# AudioOutput.net
KiCad netlist of a schematic drawn in EAGLE
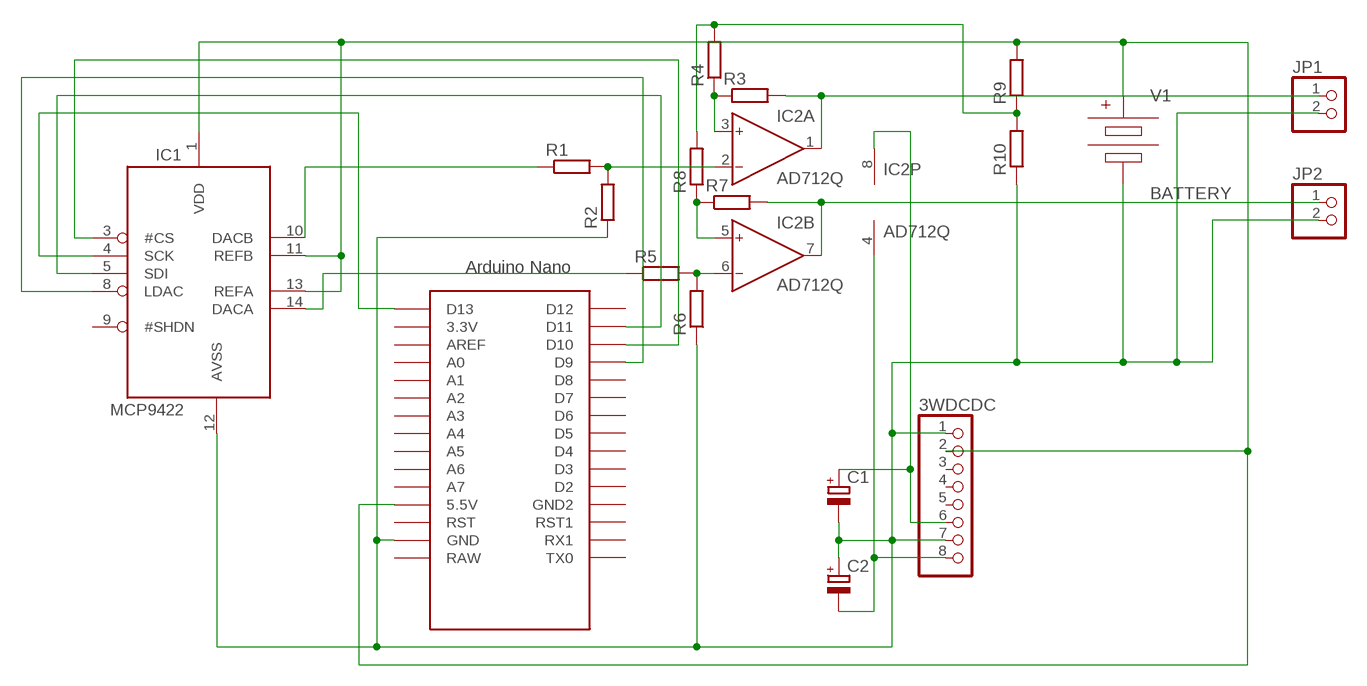
[diagram p0: schematic, sheet 1]

(export (version "E")
  (design (tool "Eeschema 10.0.6"))
  (components
    (comp (ref "3WDCDC")
      (value "PINHD-1X8")
      (footprint "eagle-import:1X08")
      (libsource (lib "eagle-import") (part "PINHD-1X8"))
    )
    (comp (ref "C1")
      (value "CPOL-EUE2.5-7")
      (footprint "eagle-import:E2,5-7")
      (libsource (lib "eagle-import") (part "CPOL-EUE2.5-7"))
    )
    (comp (ref "C2")
      (value "CPOL-EUE2.5-7")
      (footprint "eagle-import:E2,5-7")
      (libsource (lib "eagle-import") (part "CPOL-EUE2.5-7"))
    )
    (comp (ref "IC1")
      (value "MCP9422")
      (footprint "eagle-import:DIL14")
      (libsource (lib "eagle-import") (part "MCP9422"))
    )
    (comp (ref "IC2")
      (value "AD712Q")
      (footprint "eagle-import:DIL08")
      (fields (field (name "MF") "ALTERA CORPORATION") (field (name "MPN") "AD712AQ"))
      (libsource (lib "eagle-import") (part "AD712Q"))
    )
    (comp (ref "JP1")
      (value "PINHD-1X2")
      (footprint "eagle-import:1X02")
      (libsource (lib "eagle-import") (part "PINHD-1X2"))
    )
    (comp (ref "JP2")
      (value "PINHD-1X2")
      (footprint "eagle-import:1X02")
      (libsource (lib "eagle-import") (part "PINHD-1X2"))
    )
    (comp (ref "R1")
      (value "R-EU_0207/10")
      (footprint "eagle-import:0207_10")
      (libsource (lib "eagle-import") (part "R-EU_0207/10"))
    )
    (comp (ref "R2")
      (value "R-EU_0207/10")
      (footprint "eagle-import:0207_10")
      (libsource (lib "eagle-import") (part "R-EU_0207/10"))
    )
    (comp (ref "R3")
      (value "R-EU_0207/10")
      (footprint "eagle-import:0207_10")
      (libsource (lib "eagle-import") (part "R-EU_0207/10"))
    )
    (comp (ref "R4")
      (value "R-EU_0207/10")
      (footprint "eagle-import:0207_10")
      (libsource (lib "eagle-import") (part "R-EU_0207/10"))
    )
    (comp (ref "R5")
      (value "R-EU_0207/10")
      (footprint "eagle-import:0207_10")
      (libsource (lib "eagle-import") (part "R-EU_0207/10"))
    )
    (comp (ref "R6")
      (value "R-EU_0207/10")
      (footprint "eagle-import:0207_10")
      (libsource (lib "eagle-import") (part "R-EU_0207/10"))
    )
    (comp (ref "R7")
      (value "R-EU_0207/10")
      (footprint "eagle-import:0207_10")
      (libsource (lib "eagle-import") (part "R-EU_0207/10"))
    )
    (comp (ref "R8")
      (value "R-EU_0207/10")
      (footprint "eagle-import:0207_10")
      (libsource (lib "eagle-import") (part "R-EU_0207/10"))
    )
    (comp (ref "R9")
      (value "R-EU_0207/10")
      (footprint "eagle-import:0207_10")
      (libsource (lib "eagle-import") (part "R-EU_0207/10"))
    )
    (comp (ref "R10")
      (value "R-EU_0207/10")
      (footprint "eagle-import:0207_10")
      (libsource (lib "eagle-import") (part "R-EU_0207/10"))
    )
    (comp (ref "U$1")
      (value "NANO")
      (footprint "eagle-import:NANO")
      (libsource (lib "eagle-import") (part "NANO"))
    )
    (comp (ref "V1")
      (value "BATTERY")
      (footprint "eagle-import:3V60R")
      (libsource (lib "eagle-import") (part "BATTERY"))
    )
  )
  (nets
    (net (code "1") (name "Net-(IC1-#CS)") (class "Default")
      (node (ref "IC1") (pin "3") (pinfunction "#CS_3") (pintype "input"))
      (node (ref "U$1") (pin "D10") (pinfunction "D10_D10") (pintype "bidirectional"))
    )
    (net (code "2") (name "Net-(IC1-AVSS)") (class "Default")
      (node (ref "3WDCDC") (pin "1") (pinfunction "1_1") (pintype "passive"))
      (node (ref "3WDCDC") (pin "7") (pinfunction "7_7") (pintype "passive"))
      (node (ref "C1") (pin "-") (pinfunction "-_-") (pintype "passive"))
      (node (ref "C2") (pin "+") (pinfunction "+_+") (pintype "passive"))
      (node (ref "IC1") (pin "12") (pinfunction "AVSS_12") (pintype "power_in"))
      (node (ref "JP1") (pin "2") (pinfunction "2_2") (pintype "passive"))
      (node (ref "JP2") (pin "2") (pinfunction "2_2") (pintype "passive"))
      (node (ref "R10") (pin "1") (pinfunction "1_1") (pintype "passive"))
      (node (ref "R2") (pin "1") (pinfunction "1_1") (pintype "passive"))
      (node (ref "R6") (pin "1") (pinfunction "1_1") (pintype "passive"))
      (node (ref "U$1") (pin "GND") (pinfunction "GND_GND") (pintype "bidirectional"))
      (node (ref "V1") (pin "-") (pinfunction "-_-") (pintype "passive"))
    )
    (net (code "3") (name "Net-(IC1-DACA)") (class "Default")
      (node (ref "IC1") (pin "14") (pinfunction "DACA_14") (pintype "output"))
      (node (ref "R5") (pin "1") (pinfunction "1_1") (pintype "passive"))
    )
    (net (code "4") (name "Net-(IC1-DACB)") (class "Default")
      (node (ref "IC1") (pin "10") (pinfunction "DACB_10") (pintype "output"))
      (node (ref "R1") (pin "1") (pinfunction "1_1") (pintype "passive"))
    )
    (net (code "5") (name "Net-(IC1-LDAC)") (class "Default")
      (node (ref "IC1") (pin "8") (pinfunction "LDAC_8") (pintype "input"))
      (node (ref "U$1") (pin "D9") (pinfunction "D9_D9") (pintype "bidirectional"))
    )
    (net (code "6") (name "Net-(IC1-REFA)") (class "Default")
      (node (ref "3WDCDC") (pin "2") (pinfunction "2_2") (pintype "passive"))
      (node (ref "IC1") (pin "1") (pinfunction "VDD_1") (pintype "power_in"))
      (node (ref "IC1") (pin "11") (pinfunction "REFB_11") (pintype "input"))
      (node (ref "IC1") (pin "13") (pinfunction "REFA_13") (pintype "input"))
      (node (ref "R9") (pin "2") (pinfunction "2_2") (pintype "passive"))
      (node (ref "U$1") (pin "5V") (pinfunction "5.5V_5V") (pintype "bidirectional"))
      (node (ref "V1") (pin "+") (pinfunction "+_+") (pintype "passive"))
      (node (ref "V1") (pin "+@1") (pinfunction "+_+@1") (pintype "passive"))
    )
    (net (code "7") (name "Net-(IC1-SCK)") (class "Default")
      (node (ref "IC1") (pin "4") (pinfunction "SCK_4") (pintype "input"))
      (node (ref "U$1") (pin "D13") (pinfunction "D13_D13") (pintype "bidirectional"))
    )
    (net (code "8") (name "Net-(IC1-SDI)") (class "Default")
      (node (ref "IC1") (pin "5") (pinfunction "SDI_5") (pintype "input"))
      (node (ref "U$1") (pin "D11") (pinfunction "D11_D11") (pintype "bidirectional"))
    )
    (net (code "9") (name "Net-(IC2A-IN+)") (class "Default")
      (node (ref "IC2") (pin "3") (pinfunction "IN+_3") (pintype "input"))
      (node (ref "R3") (pin "1") (pinfunction "1_1") (pintype "passive"))
      (node (ref "R4") (pin "1") (pinfunction "1_1") (pintype "passive"))
    )
    (net (code "10") (name "Net-(IC2A-IN-)") (class "Default")
      (node (ref "IC2") (pin "2") (pinfunction "IN-_2") (pintype "input"))
      (node (ref "R1") (pin "2") (pinfunction "2_2") (pintype "passive"))
      (node (ref "R2") (pin "2") (pinfunction "2_2") (pintype "passive"))
    )
    (net (code "11") (name "Net-(IC2A-OUT)") (class "Default")
      (node (ref "IC2") (pin "1") (pinfunction "OUT_1") (pintype "output"))
      (node (ref "JP1") (pin "1") (pinfunction "1_1") (pintype "passive"))
      (node (ref "R3") (pin "2") (pinfunction "2_2") (pintype "passive"))
    )
    (net (code "12") (name "Net-(IC2B-IN+)") (class "Default")
      (node (ref "IC2") (pin "5") (pinfunction "IN+_5") (pintype "input"))
      (node (ref "R7") (pin "1") (pinfunction "1_1") (pintype "passive"))
      (node (ref "R8") (pin "1") (pinfunction "1_1") (pintype "passive"))
    )
    (net (code "13") (name "Net-(IC2B-IN-)") (class "Default")
      (node (ref "IC2") (pin "6") (pinfunction "IN-_6") (pintype "input"))
      (node (ref "R5") (pin "2") (pinfunction "2_2") (pintype "passive"))
      (node (ref "R6") (pin "2") (pinfunction "2_2") (pintype "passive"))
    )
    (net (code "14") (name "Net-(IC2B-OUT)") (class "Default")
      (node (ref "IC2") (pin "7") (pinfunction "OUT_7") (pintype "output"))
      (node (ref "JP2") (pin "1") (pinfunction "1_1") (pintype "passive"))
      (node (ref "R7") (pin "2") (pinfunction "2_2") (pintype "passive"))
    )
    (net (code "15") (name "Net-(IC2C-V+)") (class "Default")
      (node (ref "3WDCDC") (pin "6") (pinfunction "6_6") (pintype "passive"))
      (node (ref "C1") (pin "+") (pinfunction "+_+") (pintype "passive"))
      (node (ref "IC2") (pin "8") (pinfunction "V+_8") (pintype "power_in"))
    )
    (net (code "16") (name "Net-(IC2C-V-)") (class "Default")
      (node (ref "3WDCDC") (pin "8") (pinfunction "8_8") (pintype "passive"))
      (node (ref "C2") (pin "-") (pinfunction "-_-") (pintype "passive"))
      (node (ref "IC2") (pin "4") (pinfunction "V-_4") (pintype "power_in"))
    )
    (net (code "17") (name "Net-(R10-Pad2)") (class "Default")
      (node (ref "R10") (pin "2") (pinfunction "2_2") (pintype "passive"))
      (node (ref "R4") (pin "2") (pinfunction "2_2") (pintype "passive"))
      (node (ref "R8") (pin "2") (pinfunction "2_2") (pintype "passive"))
      (node (ref "R9") (pin "1") (pinfunction "1_1") (pintype "passive"))
    )
    (net (code "18") (name "unconnected-(3WDCDC-Pad3)") (class "Default")
      (node (ref "3WDCDC") (pin "3") (pinfunction "3_3") (pintype "passive"))
    )
    (net (code "19") (name "unconnected-(3WDCDC-Pad4)") (class "Default")
      (node (ref "3WDCDC") (pin "4") (pinfunction "4_4") (pintype "passive"))
    )
    (net (code "20") (name "unconnected-(3WDCDC-Pad5)") (class "Default")
      (node (ref "3WDCDC") (pin "5") (pinfunction "5_5") (pintype "passive"))
    )
    (net (code "21") (name "unconnected-(IC1-#SHDN-Pad9)") (class "Default")
      (node (ref "IC1") (pin "9") (pinfunction "#SHDN_9") (pintype "input"))
    )
    (net (code "22") (name "unconnected-(U$1-GND2-PadGND1)") (class "Default")
      (node (ref "U$1") (pin "GND1") (pinfunction "GND2_GND1") (pintype "bidirectional"))
    )
    (net (code "23") (name "unconnected-(U$1-Pad3.3V)") (class "Default")
      (node (ref "U$1") (pin "3.3V") (pinfunction "3.3V_3.3V") (pintype "bidirectional"))
    )
    (net (code "24") (name "unconnected-(U$1-PadA0)") (class "Default")
      (node (ref "U$1") (pin "A0") (pinfunction "A0_A0") (pintype "bidirectional"))
    )
    (net (code "25") (name "unconnected-(U$1-PadA1)") (class "Default")
      (node (ref "U$1") (pin "A1") (pinfunction "A1_A1") (pintype "bidirectional"))
    )
    (net (code "26") (name "unconnected-(U$1-PadA2)") (class "Default")
      (node (ref "U$1") (pin "A2") (pinfunction "A2_A2") (pintype "bidirectional"))
    )
    (net (code "27") (name "unconnected-(U$1-PadA3)") (class "Default")
      (node (ref "U$1") (pin "A3") (pinfunction "A3_A3") (pintype "bidirectional"))
    )
    (net (code "28") (name "unconnected-(U$1-PadA4)") (class "Default")
      (node (ref "U$1") (pin "A4") (pinfunction "A4_A4") (pintype "bidirectional"))
    )
    (net (code "29") (name "unconnected-(U$1-PadA5)") (class "Default")
      (node (ref "U$1") (pin "A5") (pinfunction "A5_A5") (pintype "bidirectional"))
    )
    (net (code "30") (name "unconnected-(U$1-PadA6)") (class "Default")
      (node (ref "U$1") (pin "A6") (pinfunction "A6_A6") (pintype "bidirectional"))
    )
    (net (code "31") (name "unconnected-(U$1-PadA7)") (class "Default")
      (node (ref "U$1") (pin "A7") (pinfunction "A7_A7") (pintype "bidirectional"))
    )
    (net (code "32") (name "unconnected-(U$1-PadAREF)") (class "Default")
      (node (ref "U$1") (pin "AREF") (pinfunction "AREF_AREF") (pintype "bidirectional"))
    )
    (net (code "33") (name "unconnected-(U$1-PadD2)") (class "Default")
      (node (ref "U$1") (pin "D2") (pinfunction "D2_D2") (pintype "bidirectional"))
    )
    (net (code "34") (name "unconnected-(U$1-PadD3)") (class "Default")
      (node (ref "U$1") (pin "D3") (pinfunction "D3_D3") (pintype "bidirectional"))
    )
    (net (code "35") (name "unconnected-(U$1-PadD4)") (class "Default")
      (node (ref "U$1") (pin "D4") (pinfunction "D4_D4") (pintype "bidirectional"))
    )
    (net (code "36") (name "unconnected-(U$1-PadD5)") (class "Default")
      (node (ref "U$1") (pin "D5") (pinfunction "D5_D5") (pintype "bidirectional"))
    )
    (net (code "37") (name "unconnected-(U$1-PadD6)") (class "Default")
      (node (ref "U$1") (pin "D6") (pinfunction "D6_D6") (pintype "bidirectional"))
    )
    (net (code "38") (name "unconnected-(U$1-PadD7)") (class "Default")
      (node (ref "U$1") (pin "D7") (pinfunction "D7_D7") (pintype "bidirectional"))
    )
    (net (code "39") (name "unconnected-(U$1-PadD8)") (class "Default")
      (node (ref "U$1") (pin "D8") (pinfunction "D8_D8") (pintype "bidirectional"))
    )
    (net (code "40") (name "unconnected-(U$1-PadD12)") (class "Default")
      (node (ref "U$1") (pin "D12") (pinfunction "D12_D12") (pintype "bidirectional"))
    )
    (net (code "41") (name "unconnected-(U$1-PadICSP1)") (class "Default")
      (node (ref "U$1") (pin "ICSP1") (pinfunction "ICSP1_ICSP1") (pintype "bidirectional"))
    )
    (net (code "42") (name "unconnected-(U$1-PadICSP2)") (class "Default")
      (node (ref "U$1") (pin "ICSP2") (pinfunction "ICSP2_ICSP2") (pintype "bidirectional"))
    )
    (net (code "43") (name "unconnected-(U$1-PadICSP3)") (class "Default")
      (node (ref "U$1") (pin "ICSP3") (pinfunction "ICSP3_ICSP3") (pintype "bidirectional"))
    )
    (net (code "44") (name "unconnected-(U$1-PadICSP4)") (class "Default")
      (node (ref "U$1") (pin "ICSP4") (pinfunction "ICSP4_ICSP4") (pintype "bidirectional"))
    )
    (net (code "45") (name "unconnected-(U$1-PadICSP5)") (class "Default")
      (node (ref "U$1") (pin "ICSP5") (pinfunction "ICSP5_ICSP5") (pintype "bidirectional"))
    )
    (net (code "46") (name "unconnected-(U$1-PadICSP6)") (class "Default")
      (node (ref "U$1") (pin "ICSP6") (pinfunction "ICSP6_ICSP6") (pintype "bidirectional"))
    )
    (net (code "47") (name "unconnected-(U$1-PadRAW)") (class "Default")
      (node (ref "U$1") (pin "RAW") (pinfunction "RAW_RAW") (pintype "bidirectional"))
    )
    (net (code "48") (name "unconnected-(U$1-PadRST)") (class "Default")
      (node (ref "U$1") (pin "RST") (pinfunction "RST_RST") (pintype "bidirectional"))
    )
    (net (code "49") (name "unconnected-(U$1-PadRST1)") (class "Default")
      (node (ref "U$1") (pin "RST1") (pinfunction "RST1_RST1") (pintype "bidirectional"))
    )
    (net (code "50") (name "unconnected-(U$1-PadRX1)") (class "Default")
      (node (ref "U$1") (pin "RX1") (pinfunction "RX1_RX1") (pintype "bidirectional"))
    )
    (net (code "51") (name "unconnected-(U$1-PadTX0)") (class "Default")
      (node (ref "U$1") (pin "TX0") (pinfunction "TX0_TX0") (pintype "bidirectional"))
    )
  )
)
